# Boot_section.net
KiCad netlist of a schematic drawn in Altium Designer
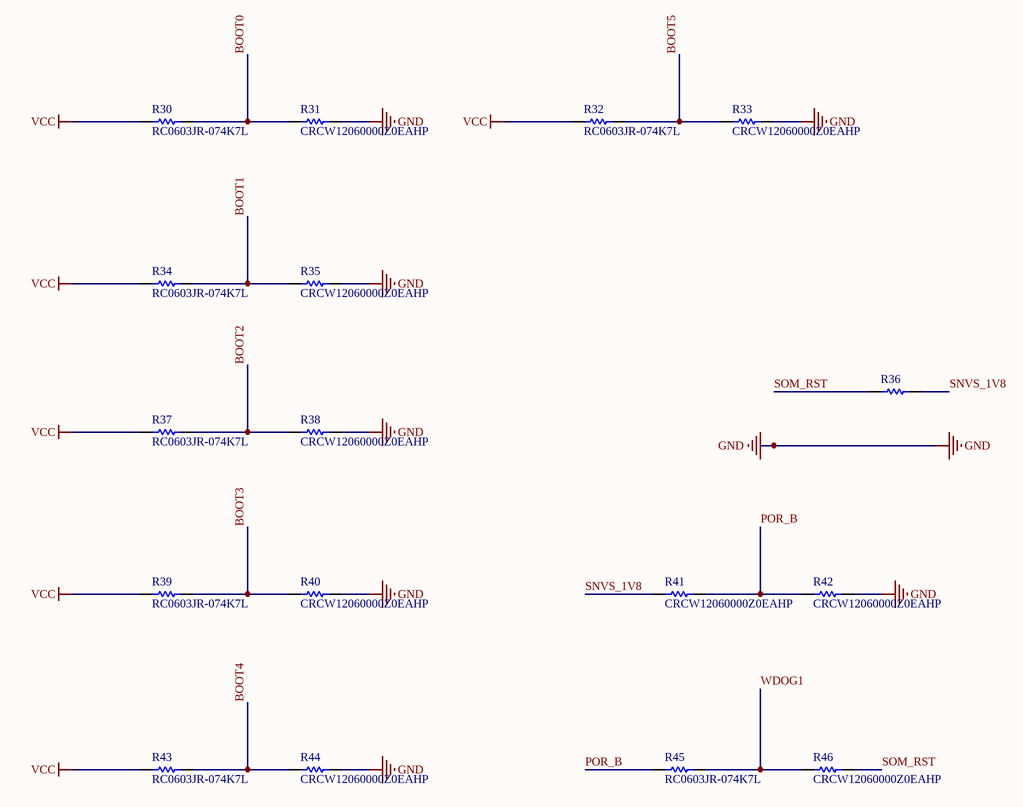
[diagram p0: Boot_section.SchDoc]

(export (version "E")
  (design (tool "Eeschema 10.0.6"))
  (components
    (comp (ref "R30")
      (value "RC0603JR-074K7L")
      (footprint "RESC1608X55X25ML10T15")
      (description "Chip Resistor, 4.7 KOhm, +/- 5%, 100 mW, -55 to 155 degC, 0603 (1608 Metric), RoHS, Tape and Reel")
      (fields (field (name "TOLERANCE") "5%") (field (name "MANUFACTURER") "Yageo"))
      (libsource (lib "Altium Content Vault") (part "RES-2"))
    )
    (comp (ref "R31")
      (value "CRCW12060000Z0EAHP")
      (footprint "RESC3116X65X50ML20T20")
      (fields (field (name "MANUFACTURER") "Vishay Dale"))
      (libsource (lib "Altium Content Vault") (part "RES"))
    )
    (comp (ref "R32")
      (value "RC0603JR-074K7L")
      (footprint "RESC1608X55X25ML10T15")
      (description "Chip Resistor, 4.7 KOhm, +/- 5%, 100 mW, -55 to 155 degC, 0603 (1608 Metric), RoHS, Tape and Reel")
      (fields (field (name "TOLERANCE") "5%") (field (name "MANUFACTURER") "Yageo"))
      (libsource (lib "Altium Content Vault") (part "RES-2"))
    )
    (comp (ref "R33")
      (value "CRCW12060000Z0EAHP")
      (footprint "RESC3116X65X50ML20T20")
      (fields (field (name "MANUFACTURER") "Vishay Dale"))
      (libsource (lib "Altium Content Vault") (part "RES"))
    )
    (comp (ref "R34")
      (value "RC0603JR-074K7L")
      (footprint "RESC1608X55X25ML10T15")
      (description "Chip Resistor, 4.7 KOhm, +/- 5%, 100 mW, -55 to 155 degC, 0603 (1608 Metric), RoHS, Tape and Reel")
      (fields (field (name "TOLERANCE") "5%") (field (name "MANUFACTURER") "Yageo"))
      (libsource (lib "Altium Content Vault") (part "RES-2"))
    )
    (comp (ref "R35")
      (value "CRCW12060000Z0EAHP")
      (footprint "RESC3116X65X50ML20T20")
      (fields (field (name "MANUFACTURER") "Vishay Dale"))
      (libsource (lib "Altium Content Vault") (part "RES"))
    )
    (comp (ref "R36")
      (value "ERJ-6GEYJ104V")
      (footprint "RESC2013X70X40NL20T20")
      (fields (field (name "MANUFACTURER") "Panasonic"))
      (libsource (lib "Altium Content Vault") (part "RES"))
    )
    (comp (ref "R37")
      (value "RC0603JR-074K7L")
      (footprint "RESC1608X55X25ML10T15")
      (description "Chip Resistor, 4.7 KOhm, +/- 5%, 100 mW, -55 to 155 degC, 0603 (1608 Metric), RoHS, Tape and Reel")
      (fields (field (name "TOLERANCE") "5%") (field (name "MANUFACTURER") "Yageo"))
      (libsource (lib "Altium Content Vault") (part "RES-2"))
    )
    (comp (ref "R38")
      (value "CRCW12060000Z0EAHP")
      (footprint "RESC3116X65X50ML20T20")
      (fields (field (name "MANUFACTURER") "Vishay Dale"))
      (libsource (lib "Altium Content Vault") (part "RES"))
    )
    (comp (ref "R39")
      (value "RC0603JR-074K7L")
      (footprint "RESC1608X55X25ML10T15")
      (description "Chip Resistor, 4.7 KOhm, +/- 5%, 100 mW, -55 to 155 degC, 0603 (1608 Metric), RoHS, Tape and Reel")
      (fields (field (name "TOLERANCE") "5%") (field (name "MANUFACTURER") "Yageo"))
      (libsource (lib "Altium Content Vault") (part "RES-2"))
    )
    (comp (ref "R40")
      (value "CRCW12060000Z0EAHP")
      (footprint "RESC3116X65X50ML20T20")
      (fields (field (name "MANUFACTURER") "Vishay Dale"))
      (libsource (lib "Altium Content Vault") (part "RES"))
    )
    (comp (ref "R41")
      (value "CRCW12060000Z0EAHP")
      (footprint "RESC3116X65X50ML20T20")
      (fields (field (name "MANUFACTURER") "Vishay Dale"))
      (libsource (lib "Altium Content Vault") (part "RES"))
    )
    (comp (ref "R42")
      (value "CRCW12060000Z0EAHP")
      (footprint "RESC3116X65X50ML20T20")
      (fields (field (name "MANUFACTURER") "Vishay Dale"))
      (libsource (lib "Altium Content Vault") (part "RES"))
    )
    (comp (ref "R43")
      (value "RC0603JR-074K7L")
      (footprint "RESC1608X55X25ML10T15")
      (description "Chip Resistor, 4.7 KOhm, +/- 5%, 100 mW, -55 to 155 degC, 0603 (1608 Metric), RoHS, Tape and Reel")
      (fields (field (name "TOLERANCE") "5%") (field (name "MANUFACTURER") "Yageo"))
      (libsource (lib "Altium Content Vault") (part "RES-2"))
    )
    (comp (ref "R44")
      (value "CRCW12060000Z0EAHP")
      (footprint "RESC3116X65X50ML20T20")
      (fields (field (name "MANUFACTURER") "Vishay Dale"))
      (libsource (lib "Altium Content Vault") (part "RES"))
    )
    (comp (ref "R45")
      (value "RC0603JR-074K7L")
      (footprint "RESC1608X55X25ML10T15")
      (description "Chip Resistor, 4.7 KOhm, +/- 5%, 100 mW, -55 to 155 degC, 0603 (1608 Metric), RoHS, Tape and Reel")
      (fields (field (name "TOLERANCE") "5%") (field (name "MANUFACTURER") "Yageo"))
      (libsource (lib "Altium Content Vault") (part "RES-2"))
    )
    (comp (ref "R46")
      (value "CRCW12060000Z0EAHP")
      (footprint "RESC3116X65X50ML20T20")
      (fields (field (name "MANUFACTURER") "Vishay Dale"))
      (libsource (lib "Altium Content Vault") (part "RES"))
    )
  )
  (nets
    (net (code "1") (name "/BOOT0") (class "Default")
      (node (ref "R30") (pin "1") (pinfunction "1_1") (pintype "passive"))
      (node (ref "R31") (pin "1") (pinfunction "1_1") (pintype "passive"))
    )
    (net (code "2") (name "/BOOT1") (class "Default")
      (node (ref "R34") (pin "1") (pinfunction "1_1") (pintype "passive"))
      (node (ref "R35") (pin "1") (pinfunction "1_1") (pintype "passive"))
    )
    (net (code "3") (name "/BOOT2") (class "Default")
      (node (ref "R37") (pin "1") (pinfunction "1_1") (pintype "passive"))
      (node (ref "R38") (pin "1") (pinfunction "1_1") (pintype "passive"))
    )
    (net (code "4") (name "/BOOT3") (class "Default")
      (node (ref "R39") (pin "1") (pinfunction "1_1") (pintype "passive"))
      (node (ref "R40") (pin "1") (pinfunction "1_1") (pintype "passive"))
    )
    (net (code "5") (name "/BOOT4") (class "Default")
      (node (ref "R43") (pin "1") (pinfunction "1_1") (pintype "passive"))
      (node (ref "R44") (pin "1") (pinfunction "1_1") (pintype "passive"))
    )
    (net (code "6") (name "/BOOT5") (class "Default")
      (node (ref "R32") (pin "1") (pinfunction "1_1") (pintype "passive"))
      (node (ref "R33") (pin "1") (pinfunction "1_1") (pintype "passive"))
    )
    (net (code "7") (name "/POR_B") (class "Default")
      (node (ref "R41") (pin "2") (pinfunction "2_2") (pintype "passive"))
      (node (ref "R42") (pin "1") (pinfunction "1_1") (pintype "passive"))
      (node (ref "R45") (pin "2") (pinfunction "2_2") (pintype "passive"))
    )
    (net (code "8") (name "/SNVS_1V8") (class "Default")
      (node (ref "R36") (pin "2") (pinfunction "2_2") (pintype "passive"))
      (node (ref "R41") (pin "1") (pinfunction "1_1") (pintype "passive"))
    )
    (net (code "9") (name "/SOM_RST") (class "Default")
      (node (ref "R36") (pin "1") (pinfunction "1_1") (pintype "passive"))
      (node (ref "R46") (pin "2") (pinfunction "2_2") (pintype "passive"))
    )
    (net (code "10") (name "/WDOG1") (class "Default")
      (node (ref "R45") (pin "1") (pinfunction "1_1") (pintype "passive"))
      (node (ref "R46") (pin "1") (pinfunction "1_1") (pintype "passive"))
    )
    (net (code "11") (name "GND") (class "Default")
      (node (ref "R31") (pin "2") (pinfunction "2_2") (pintype "passive"))
      (node (ref "R33") (pin "2") (pinfunction "2_2") (pintype "passive"))
      (node (ref "R35") (pin "2") (pinfunction "2_2") (pintype "passive"))
      (node (ref "R38") (pin "2") (pinfunction "2_2") (pintype "passive"))
      (node (ref "R40") (pin "2") (pinfunction "2_2") (pintype "passive"))
      (node (ref "R42") (pin "2") (pinfunction "2_2") (pintype "passive"))
      (node (ref "R44") (pin "2") (pinfunction "2_2") (pintype "passive"))
    )
    (net (code "12") (name "VCC") (class "Default")
      (node (ref "R30") (pin "2") (pinfunction "2_2") (pintype "passive"))
      (node (ref "R32") (pin "2") (pinfunction "2_2") (pintype "passive"))
      (node (ref "R34") (pin "2") (pinfunction "2_2") (pintype "passive"))
      (node (ref "R37") (pin "2") (pinfunction "2_2") (pintype "passive"))
      (node (ref "R39") (pin "2") (pinfunction "2_2") (pintype "passive"))
      (node (ref "R43") (pin "2") (pinfunction "2_2") (pintype "passive"))
    )
  )
)
